# Peripherals.net
KiCad netlist of a schematic drawn in Altium Designer
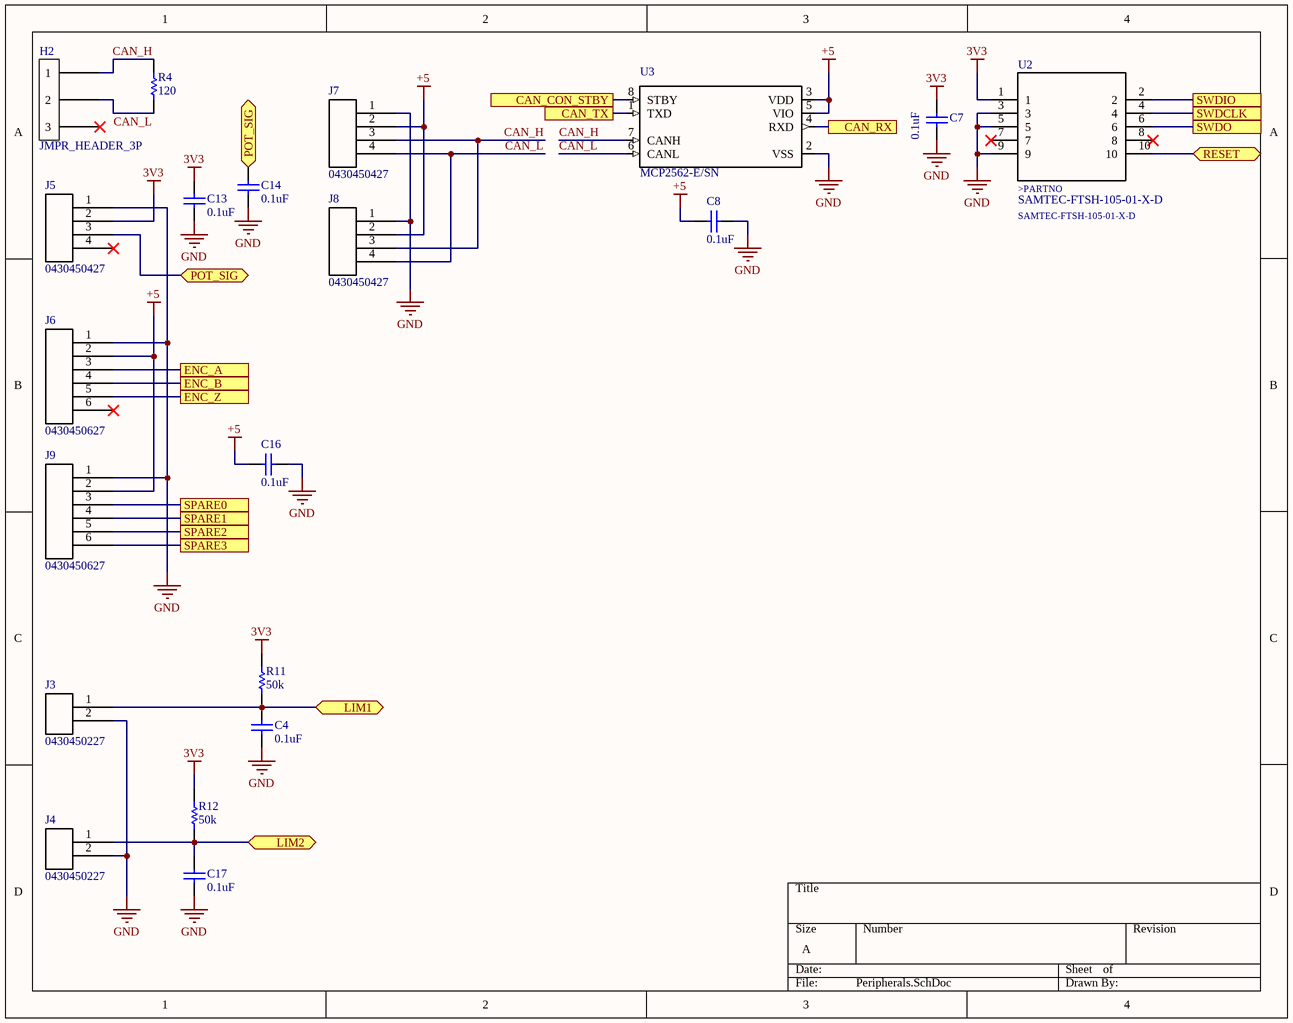
[diagram p0: Peripherals.SchDoc]

(export (version "E")
  (design (tool "Eeschema 10.0.6"))
  (components
    (comp (ref "C4")
      (value "0.1uF")
      (footprint "RESC2013X60X35LL10T20")
      (description "Capacitor (Semiconductor SIM Model)")
      (fields (field (name "Comment") "Cap Semi") (field (name "PUBLISHER") "Altium Limited"))
      (libsource (lib "Miscellaneous Devices") (part "Cap Semi"))
    )
    (comp (ref "C7")
      (value "0.1uF")
      (footprint "RESC2013X60X35LL10T20")
      (description "Capacitor (Semiconductor SIM Model)")
      (fields (field (name "Comment") "Cap Semi") (field (name "PUBLISHER") "Altium Limited"))
      (libsource (lib "Miscellaneous Devices") (part "Cap Semi"))
    )
    (comp (ref "C8")
      (value "0.1uF")
      (footprint "RESC2013X60X35LL10T20")
      (description "Capacitor (Semiconductor SIM Model)")
      (fields (field (name "Comment") "Cap Semi") (field (name "PUBLISHER") "Altium Limited"))
      (libsource (lib "Miscellaneous Devices") (part "Cap Semi"))
    )
    (comp (ref "C13")
      (value "0.1uF")
      (footprint "RESC2013X60X35LL10T20")
      (description "Capacitor (Semiconductor SIM Model)")
      (fields (field (name "Comment") "Cap Semi") (field (name "PUBLISHER") "Altium Limited"))
      (libsource (lib "Miscellaneous Devices") (part "Cap Semi"))
    )
    (comp (ref "C14")
      (value "0.1uF")
      (footprint "RESC2013X60X35LL10T20")
      (description "Capacitor (Semiconductor SIM Model)")
      (fields (field (name "Comment") "Cap Semi") (field (name "PUBLISHER") "Altium Limited"))
      (libsource (lib "Miscellaneous Devices") (part "Cap Semi"))
    )
    (comp (ref "C16")
      (value "0.1uF")
      (footprint "RESC2013X60X35LL10T20")
      (description "Capacitor (Semiconductor SIM Model)")
      (fields (field (name "Comment") "Cap Semi") (field (name "PUBLISHER") "Altium Limited"))
      (libsource (lib "Miscellaneous Devices") (part "Cap Semi"))
    )
    (comp (ref "C17")
      (value "0.1uF")
      (footprint "RESC2013X60X35LL10T20")
      (description "Capacitor (Semiconductor SIM Model)")
      (fields (field (name "Comment") "Cap Semi") (field (name "PUBLISHER") "Altium Limited"))
      (libsource (lib "Miscellaneous Devices") (part "Cap Semi"))
    )
    (comp (ref "H2")
      (value "JMPR_HEADER_3P")
      (footprint "STD3P")
      (libsource (lib "Jaden") (part "JMPR_HEADER_3P"))
    )
    (comp (ref "J3")
      (value "0430450227")
      (footprint "0430450227")
      (description "Micro-fit 3.0 connector. P/N 0430450227")
      (libsource (lib "Molex Micro-Fit 3.0") (part "0430450227-Single row schematic"))
    )
    (comp (ref "J4")
      (value "0430450227")
      (footprint "0430450227")
      (description "Micro-fit 3.0 connector. P/N 0430450227")
      (libsource (lib "Molex Micro-Fit 3.0") (part "0430450227-Single row schematic"))
    )
    (comp (ref "J5")
      (value "0430450427")
      (footprint "0430450427")
      (description "Molex micro-fit 3.0 dual row header. P/N 0430450427")
      (libsource (lib "Molex Micro-Fit 3.0") (part "0430450427-Single row schematic"))
    )
    (comp (ref "J6")
      (value "0430450627")
      (footprint "0430450627")
      (description "Molex micro-fit 3.0 dual row connector. P/N 0430450627")
      (libsource (lib "Molex Micro-Fit 3.0") (part "0430450627-Single row schematic"))
    )
    (comp (ref "J7")
      (value "0430450427")
      (footprint "0430450427")
      (description "Molex micro-fit 3.0 dual row header. P/N 0430450427")
      (libsource (lib "Molex Micro-Fit 3.0") (part "0430450427-Single row schematic"))
    )
    (comp (ref "J8")
      (value "0430450427")
      (footprint "0430450427")
      (description "Molex micro-fit 3.0 dual row header. P/N 0430450427")
      (libsource (lib "Molex Micro-Fit 3.0") (part "0430450427-Single row schematic"))
    )
    (comp (ref "J9")
      (value "0430450627")
      (footprint "0430450627")
      (description "Molex micro-fit 3.0 dual row connector. P/N 0430450627")
      (libsource (lib "Molex Micro-Fit 3.0") (part "0430450627-Single row schematic"))
    )
    (comp (ref "R4")
      (value "120")
      (footprint "0805:RESC2013X60X35LL10T20")
      (libsource (lib "Jaden") (part "RES-2"))
    )
    (comp (ref "R11")
      (value "50k")
      (footprint "RESC2013X60X35LL10T20")
      (libsource (lib "Jaden") (part "RES-2"))
    )
    (comp (ref "R12")
      (value "50k")
      (footprint "0805:RESC2013X60X35LL10T20")
      (libsource (lib "Jaden") (part "RES-2"))
    )
    (comp (ref "U2")
      (value "SAMTEC-FTSH-105-01-X-D")
      (footprint "SAMTEC-FTSH-105-01-X-D")
      (description "Conn Unshrouded Header HDR 10 POS 1.27mm Solder ST Thru-Hole Automotive Tube")
      (fields (field (name "MP") "FTSH-105-01-F-D-K") (field (name "DIGI-KEY_PART_NUMBER") "SAM8909-ND"))
      (libsource (lib "SAMTEC-FTSH-105-01-X-D") (part "SAMTEC-FTSH-105-01-X-D"))
    )
    (comp (ref "U3")
      (value "MCP2562-E/SN")
      (footprint "SOIC127P600X175-8N")
      (description "Microchip MCP2562-E/SN, CAN Transceiver 1MBps 1-channel IEC 61000-4-2, 8-Pin SOIC")
      (fields (field (name "MF") "Microchip"))
      (libsource (lib "MCP2562-E_SN") (part "MCP2562-E/SN"))
    )
  )
  (nets
    (net (code "1") (name "+5") (class "Default")
      (node (ref "C16") (pin "2") (pinfunction "2_2") (pintype "passive"))
      (node (ref "C8") (pin "2") (pinfunction "2_2") (pintype "passive"))
      (node (ref "J6") (pin "2") (pintype "passive"))
      (node (ref "J7") (pin "2") (pintype "passive"))
      (node (ref "J8") (pin "2") (pintype "passive"))
      (node (ref "J9") (pin "2") (pintype "passive"))
      (node (ref "U3") (pin "3") (pinfunction "VDD_3") (pintype "power_in"))
      (node (ref "U3") (pin "5") (pinfunction "VIO_5") (pintype "power_in"))
    )
    (net (code "2") (name "/CAN_CON_STBY") (class "Default")
      (node (ref "U3") (pin "8") (pinfunction "STBY_8") (pintype "input"))
    )
    (net (code "3") (name "/CAN_H") (class "Default")
      (node (ref "H2") (pin "1") (pinfunction "1_1") (pintype "passive"))
      (node (ref "J7") (pin "3") (pintype "passive"))
      (node (ref "J8") (pin "3") (pintype "passive"))
      (node (ref "R4") (pin "1") (pinfunction "1_1") (pintype "passive"))
      (node (ref "U3") (pin "7") (pinfunction "CANH_7") (pintype "input"))
    )
    (net (code "4") (name "/CAN_L") (class "Default")
      (node (ref "H2") (pin "2") (pinfunction "2_2") (pintype "passive"))
      (node (ref "J7") (pin "4") (pintype "passive"))
      (node (ref "J8") (pin "4") (pintype "passive"))
      (node (ref "R4") (pin "2") (pinfunction "2_2") (pintype "passive"))
      (node (ref "U3") (pin "6") (pinfunction "CANL_6") (pintype "input"))
    )
    (net (code "5") (name "/CAN_RX") (class "Default")
      (node (ref "U3") (pin "4") (pinfunction "RXD_4") (pintype "output"))
    )
    (net (code "6") (name "/CAN_TX") (class "Default")
      (node (ref "U3") (pin "1") (pinfunction "TXD_1") (pintype "input"))
    )
    (net (code "7") (name "/ENC_A") (class "Default") (node (ref "J6") (pin "3") (pintype "passive")))
    (net (code "8") (name "/ENC_B") (class "Default") (node (ref "J6") (pin "4") (pintype "passive")))
    (net (code "9") (name "/ENC_Z") (class "Default") (node (ref "J6") (pin "5") (pintype "passive")))
    (net (code "10") (name "/LIM1") (class "Default")
      (node (ref "C4") (pin "1") (pinfunction "1_1") (pintype "passive"))
      (node (ref "J3") (pin "1") (pintype "passive"))
      (node (ref "R11") (pin "2") (pinfunction "2_2") (pintype "passive"))
    )
    (net (code "11") (name "/LIM2") (class "Default")
      (node (ref "C17") (pin "1") (pinfunction "1_1") (pintype "passive"))
      (node (ref "J4") (pin "1") (pintype "passive"))
      (node (ref "R12") (pin "2") (pinfunction "2_2") (pintype "passive"))
    )
    (net (code "12") (name "/POT_SIG") (class "Default")
      (node (ref "C14") (pin "1") (pinfunction "1_1") (pintype "passive"))
      (node (ref "J5") (pin "3") (pintype "passive"))
    )
    (net (code "13") (name "/RESET") (class "Default")
      (node (ref "U2") (pin "10") (pinfunction "10_10") (pintype "passive"))
    )
    (net (code "14") (name "/SPARE0") (class "Default") (node (ref "J9") (pin "3") (pintype "passive")))
    (net (code "15") (name "/SPARE1") (class "Default") (node (ref "J9") (pin "4") (pintype "passive")))
    (net (code "16") (name "/SPARE2") (class "Default") (node (ref "J9") (pin "5") (pintype "passive")))
    (net (code "17") (name "/SPARE3") (class "Default") (node (ref "J9") (pin "6") (pintype "passive")))
    (net (code "18") (name "/SWDCLK") (class "Default")
      (node (ref "U2") (pin "4") (pinfunction "4_4") (pintype "passive"))
    )
    (net (code "19") (name "/SWDIO") (class "Default")
      (node (ref "U2") (pin "2") (pinfunction "2_2") (pintype "passive"))
    )
    (net (code "20") (name "/SWDO") (class "Default")
      (node (ref "U2") (pin "6") (pinfunction "6_6") (pintype "passive"))
    )
    (net (code "21") (name "3V3") (class "Default")
      (node (ref "C13") (pin "1") (pinfunction "1_1") (pintype "passive"))
      (node (ref "C7") (pin "2") (pinfunction "2_2") (pintype "passive"))
      (node (ref "J5") (pin "2") (pintype "passive"))
      (node (ref "R11") (pin "1") (pinfunction "1_1") (pintype "passive"))
      (node (ref "R12") (pin "1") (pinfunction "1_1") (pintype "passive"))
      (node (ref "U2") (pin "1") (pinfunction "1_1") (pintype "passive"))
    )
    (net (code "22") (name "GND") (class "Default")
      (node (ref "C13") (pin "2") (pinfunction "2_2") (pintype "passive"))
      (node (ref "C14") (pin "2") (pinfunction "2_2") (pintype "passive"))
      (node (ref "C16") (pin "1") (pinfunction "1_1") (pintype "passive"))
      (node (ref "C17") (pin "2") (pinfunction "2_2") (pintype "passive"))
      (node (ref "C4") (pin "2") (pinfunction "2_2") (pintype "passive"))
      (node (ref "C7") (pin "1") (pinfunction "1_1") (pintype "passive"))
      (node (ref "C8") (pin "1") (pinfunction "1_1") (pintype "passive"))
      (node (ref "J3") (pin "2") (pintype "passive"))
      (node (ref "J4") (pin "2") (pintype "passive"))
      (node (ref "J5") (pin "1") (pintype "passive"))
      (node (ref "J6") (pin "1") (pintype "passive"))
      (node (ref "J7") (pin "1") (pintype "passive"))
      (node (ref "J8") (pin "1") (pintype "passive"))
      (node (ref "J9") (pin "1") (pintype "passive"))
      (node (ref "U2") (pin "3") (pinfunction "3_3") (pintype "passive"))
      (node (ref "U2") (pin "5") (pinfunction "5_5") (pintype "passive"))
      (node (ref "U2") (pin "9") (pinfunction "9_9") (pintype "passive"))
      (node (ref "U3") (pin "2") (pinfunction "VSS_2") (pintype "power_in"))
    )
    (net (code "23") (name "unconnected-(H2-Pad3)") (class "Default")
      (node (ref "H2") (pin "3") (pinfunction "3_3") (pintype "passive+no_connect"))
    )
    (net (code "24") (name "unconnected-(J5-Pad4)") (class "Default")
      (node (ref "J5") (pin "4") (pintype "passive+no_connect"))
    )
    (net (code "25") (name "unconnected-(J6-Pad6)") (class "Default")
      (node (ref "J6") (pin "6") (pintype "passive+no_connect"))
    )
    (net (code "26") (name "unconnected-(U2-Pad7)") (class "Default")
      (node (ref "U2") (pin "7") (pinfunction "7_7") (pintype "passive+no_connect"))
    )
    (net (code "27") (name "unconnected-(U2-Pad8)") (class "Default")
      (node (ref "U2") (pin "8") (pinfunction "8_8") (pintype "passive+no_connect"))
    )
  )
)
